# NIXIEClock_SCH.net
KiCad netlist of a schematic drawn in Altium Designer
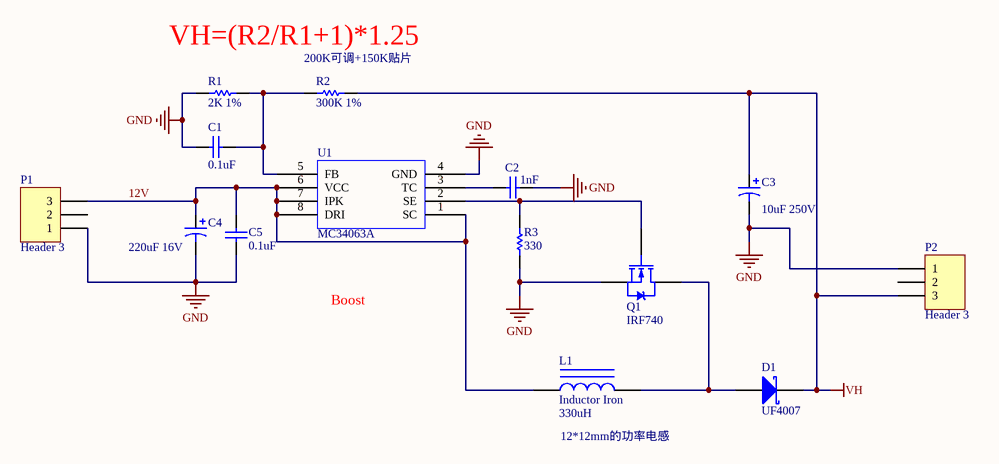
[diagram p0: NIXIEClock_SCH.SchDoc]

(export (version "E")
  (design (tool "Eeschema 10.0.6"))
  (components
    (comp (ref "C1")
      (value "0.1uF")
      (footprint "0805")
      (description "Capacitor (Semiconductor SIM Model)")
      (fields (field (name "Comment") "Cap Semi") (field (name "PUBLISHER") "Altium Limited"))
      (libsource (lib "何龙华") (part "Cap Semi"))
    )
    (comp (ref "C2")
      (value "1nF")
      (footprint "0805")
      (description "Capacitor (Semiconductor SIM Model)")
      (fields (field (name "Comment") "Cap Semi") (field (name "PUBLISHER") "Altium Limited"))
      (libsource (lib "何龙华") (part "Cap Semi"))
    )
    (comp (ref "C3")
      (value "10uF 250V")
      (footprint "C-RB-8")
      (description "Polarized Capacitor (Radial)")
      (fields (field (name "Comment") "Cap Pol1") (field (name "PUBLISHER") "Altium Limited"))
      (libsource (lib "Miscellaneous Devices") (part "Cap Pol1"))
    )
    (comp (ref "C4")
      (value "220uF 16V")
      (footprint "C-RB-6")
      (description "Polarized Capacitor (Radial)")
      (fields (field (name "Comment") "Cap Pol1") (field (name "PUBLISHER") "Altium Limited"))
      (libsource (lib "Miscellaneous Devices") (part "Cap Pol1"))
    )
    (comp (ref "C5")
      (value "0.1uF")
      (footprint "0805")
      (description "Capacitor (Semiconductor SIM Model)")
      (fields (field (name "Comment") "Cap Semi") (field (name "PUBLISHER") "Altium Limited"))
      (libsource (lib "何龙华") (part "Cap Semi"))
    )
    (comp (ref "D1")
      (value "UF4007")
      (footprint "DO-41")
      (description "Schottky Diode")
      (fields (field (name "PUBLISHER") "Altium Limited"))
      (libsource (lib "Miscellaneous Devices") (part "D Schottky"))
    )
    (comp (ref "L1")
      (value "Inductor Iron")
      (footprint "GDRH127")
      (description "Magnetic-Core Inductor")
      (fields (field (name "ALTIUM_VALUE") "330uH") (field (name "PUBLISHER") "Altium Limited"))
      (libsource (lib "Miscellaneous Devices") (part "Inductor Iron"))
    )
    (comp (ref "P1")
      (value "Header 3")
      (footprint "HDR1X3")
      (description "Header, 3-Pin")
      (fields (field (name "PUBLISHER") "Altium Limited"))
      (libsource (lib "Miscellaneous Connectors") (part "Header 3"))
    )
    (comp (ref "P2")
      (value "Header 3")
      (footprint "HDR1X3")
      (description "Header, 3-Pin")
      (fields (field (name "PUBLISHER") "Altium Limited"))
      (libsource (lib "") (part "Header 3_1"))
    )
    (comp (ref "Q1")
      (value "IRF740")
      (footprint "TO-220AB")
      (description "N-Channel Power MOSFET")
      (fields (field (name "PUBLISHER") "Altium Limited"))
      (libsource (lib "Miscellaneous Devices") (part "NMOS-2"))
    )
    (comp (ref "R1")
      (value "2K 1%")
      (footprint "0805")
      (description "Semiconductor Resistor")
      (fields (field (name "Comment") "Res Semi") (field (name "PUBLISHER") "Altium Limited"))
      (libsource (lib "何龙华") (part "Res Semi"))
    )
    (comp (ref "R2")
      (value "300K 1%")
      (footprint "0805")
      (description "Semiconductor Resistor")
      (fields (field (name "Comment") "Res Semi") (field (name "PUBLISHER") "Altium Limited"))
      (libsource (lib "何龙华") (part "Res Semi"))
    )
    (comp (ref "R3")
      (value "330")
      (footprint "0805")
      (description "Semiconductor Resistor")
      (fields (field (name "Comment") "Res Semi") (field (name "PUBLISHER") "Altium Limited"))
      (libsource (lib "何龙华") (part "Res Semi"))
    )
    (comp (ref "U1")
      (value "MC34063A")
      (footprint "SOIC8")
      (libsource (lib "NIXIEClock_SCHLib") (part "MC34063A"))
    )
  )
  (nets
    (net (code "1") (name "/12V") (class "Default")
      (node (ref "C4") (pin "1") (pinfunction "1_1") (pintype "passive"))
      (node (ref "C5") (pin "2") (pinfunction "2_2") (pintype "passive"))
      (node (ref "L1") (pin "1") (pinfunction "1_1") (pintype "passive"))
      (node (ref "P1") (pin "3") (pinfunction "3_3") (pintype "passive"))
      (node (ref "U1") (pin "1") (pinfunction "SC_1") (pintype "passive"))
      (node (ref "U1") (pin "6") (pinfunction "VCC_6") (pintype "passive"))
      (node (ref "U1") (pin "7") (pinfunction "IPK_7") (pintype "passive"))
      (node (ref "U1") (pin "8") (pinfunction "DRI_8") (pintype "passive"))
    )
    (net (code "2") (name "GND") (class "Default")
      (node (ref "C1") (pin "2") (pinfunction "2_2") (pintype "passive"))
      (node (ref "C2") (pin "1") (pinfunction "1_1") (pintype "passive"))
      (node (ref "C3") (pin "2") (pinfunction "2_2") (pintype "passive"))
      (node (ref "C4") (pin "2") (pinfunction "2_2") (pintype "passive"))
      (node (ref "C5") (pin "1") (pinfunction "1_1") (pintype "passive"))
      (node (ref "P1") (pin "1") (pinfunction "1_1") (pintype "passive"))
      (node (ref "P2") (pin "1") (pinfunction "1_1") (pintype "passive"))
      (node (ref "Q1") (pin "3") (pinfunction "S_3") (pintype "passive"))
      (node (ref "R1") (pin "2") (pinfunction "2_2") (pintype "passive"))
      (node (ref "R3") (pin "2") (pinfunction "2_2") (pintype "passive"))
      (node (ref "U1") (pin "4") (pinfunction "GND_4") (pintype "passive"))
    )
    (net (code "3") (name "Net-(D1-A)") (class "Default")
      (node (ref "D1") (pin "1") (pinfunction "A_1") (pintype "passive"))
      (node (ref "L1") (pin "2") (pinfunction "2_2") (pintype "passive"))
      (node (ref "Q1") (pin "2") (pinfunction "D_2") (pintype "passive"))
    )
    (net (code "4") (name "Net-(Q1-G)") (class "Default")
      (node (ref "Q1") (pin "1") (pinfunction "G_1") (pintype "passive"))
      (node (ref "R3") (pin "1") (pinfunction "1_1") (pintype "passive"))
      (node (ref "U1") (pin "2") (pinfunction "SE_2") (pintype "passive"))
    )
    (net (code "5") (name "Net-(U1-FB)") (class "Default")
      (node (ref "C1") (pin "1") (pinfunction "1_1") (pintype "passive"))
      (node (ref "R1") (pin "1") (pinfunction "1_1") (pintype "passive"))
      (node (ref "R2") (pin "2") (pinfunction "2_2") (pintype "passive"))
      (node (ref "U1") (pin "5") (pinfunction "FB_5") (pintype "passive"))
    )
    (net (code "6") (name "Net-(U1-TC)") (class "Default")
      (node (ref "C2") (pin "2") (pinfunction "2_2") (pintype "passive"))
      (node (ref "U1") (pin "3") (pinfunction "TC_3") (pintype "passive"))
    )
    (net (code "7") (name "VH") (class "Default")
      (node (ref "C3") (pin "1") (pinfunction "1_1") (pintype "passive"))
      (node (ref "D1") (pin "2") (pinfunction "K_2") (pintype "passive"))
      (node (ref "P2") (pin "3") (pinfunction "3_3") (pintype "passive"))
      (node (ref "R2") (pin "1") (pinfunction "1_1") (pintype "passive"))
    )
    (net (code "8") (name "unconnected-(P1-Pad2)") (class "Default")
      (node (ref "P1") (pin "2") (pinfunction "2_2") (pintype "passive"))
    )
    (net (code "9") (name "unconnected-(P2-Pad2)") (class "Default")
      (node (ref "P2") (pin "2") (pinfunction "2_2") (pintype "passive"))
    )
  )
)
